# External.net
KiCad netlist of a schematic drawn in Altium Designer
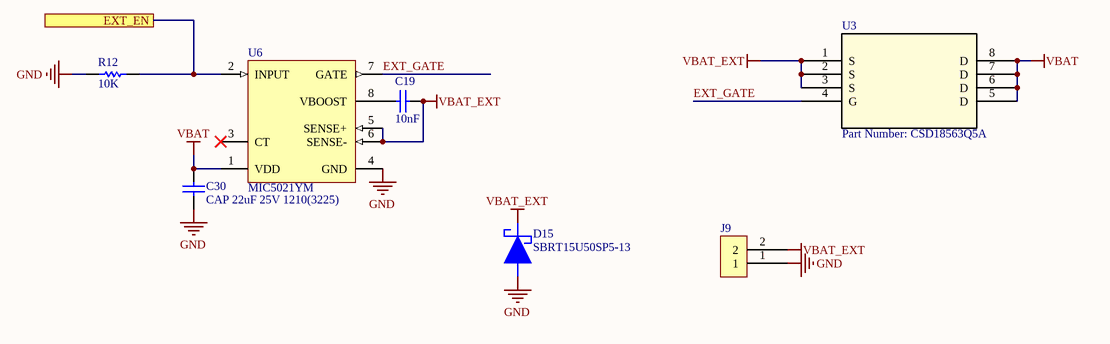
[diagram p0: External.SchDoc]

(export (version "E")
  (design (tool "Eeschema 10.0.6"))
  (components
    (comp (ref "C19")
      (value "10nF")
      (footprint "CAPC0603(1608)100_L")
      (description "CAP 10nF 25V ±2% 0603 (1608 Metric) Thickness 1mm SMD")
      (fields (field (name "TOLERANCE") "Â±2%"))
      (libsource (lib "Altium Content Vault") (part "CAP"))
    )
    (comp (ref "C30")
      (value "CAP 22uF 25V 1210(3225)")
      (footprint "CAPC1210(3225)220_L")
      (description "CAP 22uF 25V -20% to +80% 1210 (3225 Metric) Thickness 2.2mm SMD")
      (fields (field (name "TOLERANCE") "-20% to +80%"))
      (libsource (lib "Altium Content Vault") (part "CAP"))
    )
    (comp (ref "D15")
      (value "SBRT15U50SP5-13")
      (footprint "SBRT15U50SP5-13")
      (fields (field (name "MANUFACTURER") "Diodes Incorporated"))
      (libsource (lib "CMR_Miscellaneous_Devices") (part "SBRT15U50SP5-13"))
    )
    (comp (ref "J9")
      (value "~")
      (footprint "2-pin Megafit RA")
      (libsource (lib "TAUV-Lib") (part "2-pin megafit"))
    )
    (comp (ref "R12")
      (value "10K")
      (footprint "RESC0603(1608)_N")
      (description "10K 0.1W 5% 0603 (1608 Metric)  SMD")
      (fields (field (name "TOLERANCE") "5 %") (field (name "POWER") "0.1 W"))
      (libsource (lib "Altium Content Vault") (part "RES"))
    )
    (comp (ref "U3")
      (value "Part Number: CSD18563Q5A")
      (footprint "DQJ8")
      (description "No Description Available")
      (fields
        (field (name "MANUFACTURER_PART_NUMBER") "CSD18563Q5A")
        (field (name "COPYRIGHT") "Copyright (C) 2018 Accelerated Designs. All rights reserved")
      )
      (libsource (lib "Tauv-Lib") (part "CSD18563Q5A"))
    )
    (comp (ref "U6")
      (value "MIC5021YM")
      (footprint "MICL-SOICN-8LD-PL-1_V")
      (description "High-Speed High-Side MOSFET Driver, 12 to 36 V, -40 to 85 degC, 8-Pin SOIC, RoHS, Tube")
      (libsource (lib "Altium Content Vault") (part "MICL-MIC5021B_YM-8"))
    )
  )
  (nets
    (net (code "1") (name "/EXT_EN") (class "Default")
      (node (ref "R12") (pin "1") (pinfunction "1_1") (pintype "passive"))
      (node (ref "U6") (pin "2") (pinfunction "INPUT_2") (pintype "input"))
    )
    (net (code "2") (name "/EXT_GATE") (class "Default")
      (node (ref "U3") (pin "4") (pinfunction "G_4") (pintype "passive"))
      (node (ref "U6") (pin "7") (pinfunction "GATE_7") (pintype "output"))
    )
    (net (code "3") (name "GND") (class "Default")
      (node (ref "C30") (pin "1") (pinfunction "1_1") (pintype "passive"))
      (node (ref "D15") (pin "1") (pinfunction "1_1") (pintype "passive"))
      (node (ref "J9") (pin "1") (pinfunction "1_1") (pintype "passive"))
      (node (ref "R12") (pin "2") (pinfunction "2_2") (pintype "passive"))
      (node (ref "U6") (pin "4") (pinfunction "GND_4") (pintype "power_in"))
    )
    (net (code "4") (name "Net-(U6-VBOOST)") (class "Default")
      (node (ref "C19") (pin "1") (pinfunction "1_1") (pintype "passive"))
      (node (ref "U6") (pin "8") (pinfunction "VBOOST_8") (pintype "power_in"))
    )
    (net (code "5") (name "VBAT") (class "Default")
      (node (ref "C30") (pin "2") (pinfunction "2_2") (pintype "passive"))
      (node (ref "U3") (pin "5") (pinfunction "D_5") (pintype "passive"))
      (node (ref "U3") (pin "6") (pinfunction "D_6") (pintype "passive"))
      (node (ref "U3") (pin "7") (pinfunction "D_7") (pintype "passive"))
      (node (ref "U3") (pin "8") (pinfunction "D_8") (pintype "passive"))
      (node (ref "U6") (pin "1") (pinfunction "VDD_1") (pintype "power_in"))
    )
    (net (code "6") (name "VBAT_EXT") (class "Default")
      (node (ref "C19") (pin "2") (pinfunction "2_2") (pintype "passive"))
      (node (ref "D15") (pin "2") (pinfunction "2_2") (pintype "passive"))
      (node (ref "J9") (pin "2") (pinfunction "2_2") (pintype "passive"))
      (node (ref "U3") (pin "1") (pinfunction "S_1") (pintype "passive"))
      (node (ref "U3") (pin "2") (pinfunction "S_2") (pintype "passive"))
      (node (ref "U3") (pin "3") (pinfunction "S_3") (pintype "passive"))
      (node (ref "U6") (pin "5") (pinfunction "SENSE+_5") (pintype "input"))
      (node (ref "U6") (pin "6") (pinfunction "SENSE-_6") (pintype "input"))
    )
    (net (code "7") (name "unconnected-(U6-CT-Pad3)") (class "Default")
      (node (ref "U6") (pin "3") (pinfunction "CT_3") (pintype "passive+no_connect"))
    )
  )
)
